# AW9523.net
KiCad netlist of a schematic drawn in EAGLE
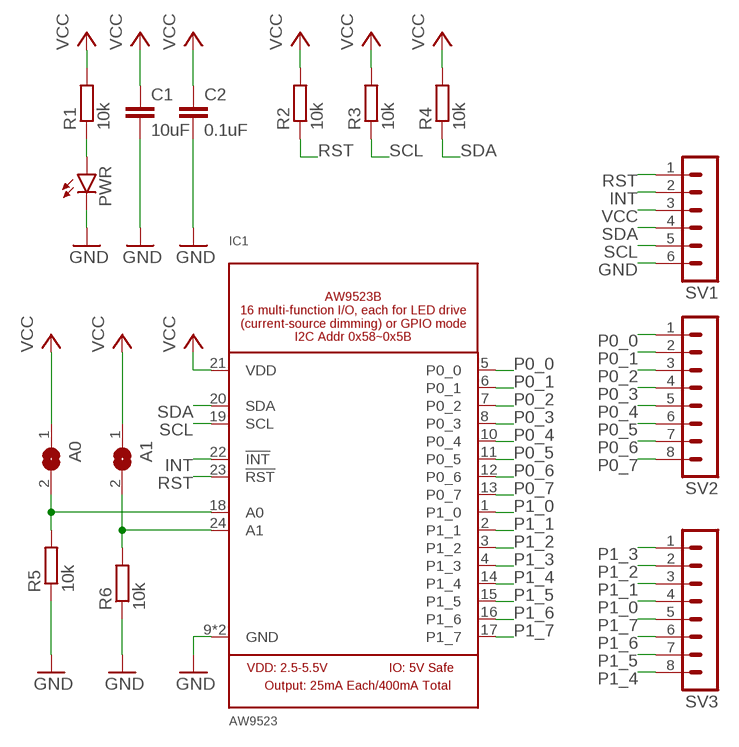
[diagram p0: schematic, sheet 1]

(export (version "E")
  (design (tool "Eeschema 10.0.6"))
  (components
    (comp (ref "A0") (value "SJ") (footprint "eagle-import:SJ") (libsource (lib "eagle-import") (part "SJ")))
    (comp (ref "A1") (value "SJ") (footprint "eagle-import:SJ") (libsource (lib "eagle-import") (part "SJ")))
    (comp (ref "C1")
      (value "10uF")
      (footprint "eagle-import:C0603")
      (libsource (lib "eagle-import") (part "C-EUC0603"))
    )
    (comp (ref "C2")
      (value "0.1uF")
      (footprint "eagle-import:C0603")
      (libsource (lib "eagle-import") (part "C-EUC0603"))
    )
    (comp (ref "IC1")
      (value "AW9523")
      (footprint "eagle-import:QFN24_4MM_SMSC")
      (libsource (lib "eagle-import") (part "AW9523"))
    )
    (comp (ref "PWR")
      (value "LEDCHIP-LED0603")
      (footprint "eagle-import:CHIP-LED0603")
      (libsource (lib "eagle-import") (part "LEDCHIP-LED0603"))
    )
    (comp (ref "R1")
      (value "10k")
      (footprint "eagle-import:R0603")
      (libsource (lib "eagle-import") (part "R-EU_R0603"))
    )
    (comp (ref "R2")
      (value "10k")
      (footprint "eagle-import:R0603")
      (libsource (lib "eagle-import") (part "R-EU_R0603"))
    )
    (comp (ref "R3")
      (value "10k")
      (footprint "eagle-import:R0603")
      (libsource (lib "eagle-import") (part "R-EU_R0603"))
    )
    (comp (ref "R4")
      (value "10k")
      (footprint "eagle-import:R0603")
      (libsource (lib "eagle-import") (part "R-EU_R0603"))
    )
    (comp (ref "R5")
      (value "10k")
      (footprint "eagle-import:R0603")
      (libsource (lib "eagle-import") (part "R-EU_R0603"))
    )
    (comp (ref "R6")
      (value "10k")
      (footprint "eagle-import:R0603")
      (libsource (lib "eagle-import") (part "R-EU_R0603"))
    )
    (comp (ref "SV1")
      (value "MA06-1")
      (footprint "eagle-import:MA06-1")
      (libsource (lib "eagle-import") (part "MA06-1"))
    )
    (comp (ref "SV2")
      (value "MA08-1")
      (footprint "eagle-import:MA08-1")
      (libsource (lib "eagle-import") (part "MA08-1"))
    )
    (comp (ref "SV3")
      (value "MA08-1")
      (footprint "eagle-import:MA08-1")
      (libsource (lib "eagle-import") (part "MA08-1"))
    )
  )
  (nets
    (net (code "1") (name "/INT") (class "Default")
      (node (ref "IC1") (pin "22") (pinfunction "~{INT}_22") (pintype "output"))
      (node (ref "SV1") (pin "2") (pinfunction "2_2") (pintype "passive"))
    )
    (net (code "2") (name "/P0_0") (class "Default")
      (node (ref "IC1") (pin "5") (pinfunction "P0_0_5") (pintype "bidirectional"))
      (node (ref "SV2") (pin "1") (pinfunction "1_1") (pintype "passive"))
    )
    (net (code "3") (name "/P0_1") (class "Default")
      (node (ref "IC1") (pin "6") (pinfunction "P0_1_6") (pintype "bidirectional"))
      (node (ref "SV2") (pin "2") (pinfunction "2_2") (pintype "passive"))
    )
    (net (code "4") (name "/P0_2") (class "Default")
      (node (ref "IC1") (pin "7") (pinfunction "P0_2_7") (pintype "bidirectional"))
      (node (ref "SV2") (pin "3") (pinfunction "3_3") (pintype "passive"))
    )
    (net (code "5") (name "/P0_3") (class "Default")
      (node (ref "IC1") (pin "8") (pinfunction "P0_3_8") (pintype "bidirectional"))
      (node (ref "SV2") (pin "4") (pinfunction "4_4") (pintype "passive"))
    )
    (net (code "6") (name "/P0_4") (class "Default")
      (node (ref "IC1") (pin "10") (pinfunction "P0_4_10") (pintype "bidirectional"))
      (node (ref "SV2") (pin "5") (pinfunction "5_5") (pintype "passive"))
    )
    (net (code "7") (name "/P0_5") (class "Default")
      (node (ref "IC1") (pin "11") (pinfunction "P0_5_11") (pintype "bidirectional"))
      (node (ref "SV2") (pin "6") (pinfunction "6_6") (pintype "passive"))
    )
    (net (code "8") (name "/P0_6") (class "Default")
      (node (ref "IC1") (pin "12") (pinfunction "P0_6_12") (pintype "bidirectional"))
      (node (ref "SV2") (pin "7") (pinfunction "7_7") (pintype "passive"))
    )
    (net (code "9") (name "/P0_7") (class "Default")
      (node (ref "IC1") (pin "13") (pinfunction "P0_7_13") (pintype "bidirectional"))
      (node (ref "SV2") (pin "8") (pinfunction "8_8") (pintype "passive"))
    )
    (net (code "10") (name "/P1_0") (class "Default")
      (node (ref "IC1") (pin "1") (pinfunction "P1_0_1") (pintype "bidirectional"))
      (node (ref "SV3") (pin "4") (pinfunction "4_4") (pintype "passive"))
    )
    (net (code "11") (name "/P1_1") (class "Default")
      (node (ref "IC1") (pin "2") (pinfunction "P1_1_2") (pintype "bidirectional"))
      (node (ref "SV3") (pin "3") (pinfunction "3_3") (pintype "passive"))
    )
    (net (code "12") (name "/P1_2") (class "Default")
      (node (ref "IC1") (pin "3") (pinfunction "P1_2_3") (pintype "bidirectional"))
      (node (ref "SV3") (pin "2") (pinfunction "2_2") (pintype "passive"))
    )
    (net (code "13") (name "/P1_3") (class "Default")
      (node (ref "IC1") (pin "4") (pinfunction "P1_3_4") (pintype "bidirectional"))
      (node (ref "SV3") (pin "1") (pinfunction "1_1") (pintype "passive"))
    )
    (net (code "14") (name "/P1_4") (class "Default")
      (node (ref "IC1") (pin "14") (pinfunction "P1_4_14") (pintype "bidirectional"))
      (node (ref "SV3") (pin "8") (pinfunction "8_8") (pintype "passive"))
    )
    (net (code "15") (name "/P1_5") (class "Default")
      (node (ref "IC1") (pin "15") (pinfunction "P1_5_15") (pintype "bidirectional"))
      (node (ref "SV3") (pin "7") (pinfunction "7_7") (pintype "passive"))
    )
    (net (code "16") (name "/P1_6") (class "Default")
      (node (ref "IC1") (pin "16") (pinfunction "P1_6_16") (pintype "bidirectional"))
      (node (ref "SV3") (pin "6") (pinfunction "6_6") (pintype "passive"))
    )
    (net (code "17") (name "/P1_7") (class "Default")
      (node (ref "IC1") (pin "17") (pinfunction "P1_7_17") (pintype "bidirectional"))
      (node (ref "SV3") (pin "5") (pinfunction "5_5") (pintype "passive"))
    )
    (net (code "18") (name "/RST") (class "Default")
      (node (ref "IC1") (pin "23") (pinfunction "~{RST}_23") (pintype "input"))
      (node (ref "R2") (pin "1") (pinfunction "1_1") (pintype "passive"))
      (node (ref "SV1") (pin "1") (pinfunction "1_1") (pintype "passive"))
    )
    (net (code "19") (name "/SCL") (class "Default")
      (node (ref "IC1") (pin "19") (pinfunction "SCL_19") (pintype "bidirectional"))
      (node (ref "R3") (pin "1") (pinfunction "1_1") (pintype "passive"))
      (node (ref "SV1") (pin "5") (pinfunction "5_5") (pintype "passive"))
    )
    (net (code "20") (name "/SDA") (class "Default")
      (node (ref "IC1") (pin "20") (pinfunction "SDA_20") (pintype "bidirectional"))
      (node (ref "R4") (pin "1") (pinfunction "1_1") (pintype "passive"))
      (node (ref "SV1") (pin "4") (pinfunction "4_4") (pintype "passive"))
    )
    (net (code "21") (name "GND") (class "Default")
      (node (ref "C1") (pin "2") (pinfunction "2_2") (pintype "passive"))
      (node (ref "C2") (pin "2") (pinfunction "2_2") (pintype "passive"))
      (node (ref "IC1") (pin "9") (pinfunction "GND_9") (pintype "power_in"))
      (node (ref "IC1") (pin "GND") (pinfunction "GND_GND") (pintype "power_in"))
      (node (ref "PWR") (pin "C") (pinfunction "C_C") (pintype "passive"))
      (node (ref "R5") (pin "1") (pinfunction "1_1") (pintype "passive"))
      (node (ref "R6") (pin "1") (pinfunction "1_1") (pintype "passive"))
      (node (ref "SV1") (pin "6") (pinfunction "6_6") (pintype "passive"))
    )
    (net (code "22") (name "Net-(IC1-A0)") (class "Default")
      (node (ref "A0") (pin "2") (pinfunction "2_2") (pintype "passive"))
      (node (ref "IC1") (pin "18") (pinfunction "A0_18") (pintype "input"))
      (node (ref "R5") (pin "2") (pinfunction "2_2") (pintype "passive"))
    )
    (net (code "23") (name "Net-(IC1-A1)") (class "Default")
      (node (ref "A1") (pin "2") (pinfunction "2_2") (pintype "passive"))
      (node (ref "IC1") (pin "24") (pinfunction "A1_24") (pintype "input"))
      (node (ref "R6") (pin "2") (pinfunction "2_2") (pintype "passive"))
    )
    (net (code "24") (name "Net-(PWR-PadA)") (class "Default")
      (node (ref "PWR") (pin "A") (pinfunction "A_A") (pintype "passive"))
      (node (ref "R1") (pin "1") (pinfunction "1_1") (pintype "passive"))
    )
    (net (code "25") (name "VCC") (class "Default")
      (node (ref "A0") (pin "1") (pinfunction "1_1") (pintype "passive"))
      (node (ref "A1") (pin "1") (pinfunction "1_1") (pintype "passive"))
      (node (ref "C1") (pin "1") (pinfunction "1_1") (pintype "passive"))
      (node (ref "C2") (pin "1") (pinfunction "1_1") (pintype "passive"))
      (node (ref "IC1") (pin "21") (pinfunction "VDD_21") (pintype "power_in"))
      (node (ref "R1") (pin "2") (pinfunction "2_2") (pintype "passive"))
      (node (ref "R2") (pin "2") (pinfunction "2_2") (pintype "passive"))
      (node (ref "R3") (pin "2") (pinfunction "2_2") (pintype "passive"))
      (node (ref "R4") (pin "2") (pinfunction "2_2") (pintype "passive"))
      (node (ref "SV1") (pin "3") (pinfunction "3_3") (pintype "passive"))
    )
  )
)
